# VlakecRemote.net
KiCad netlist of a schematic drawn in Altium Designer
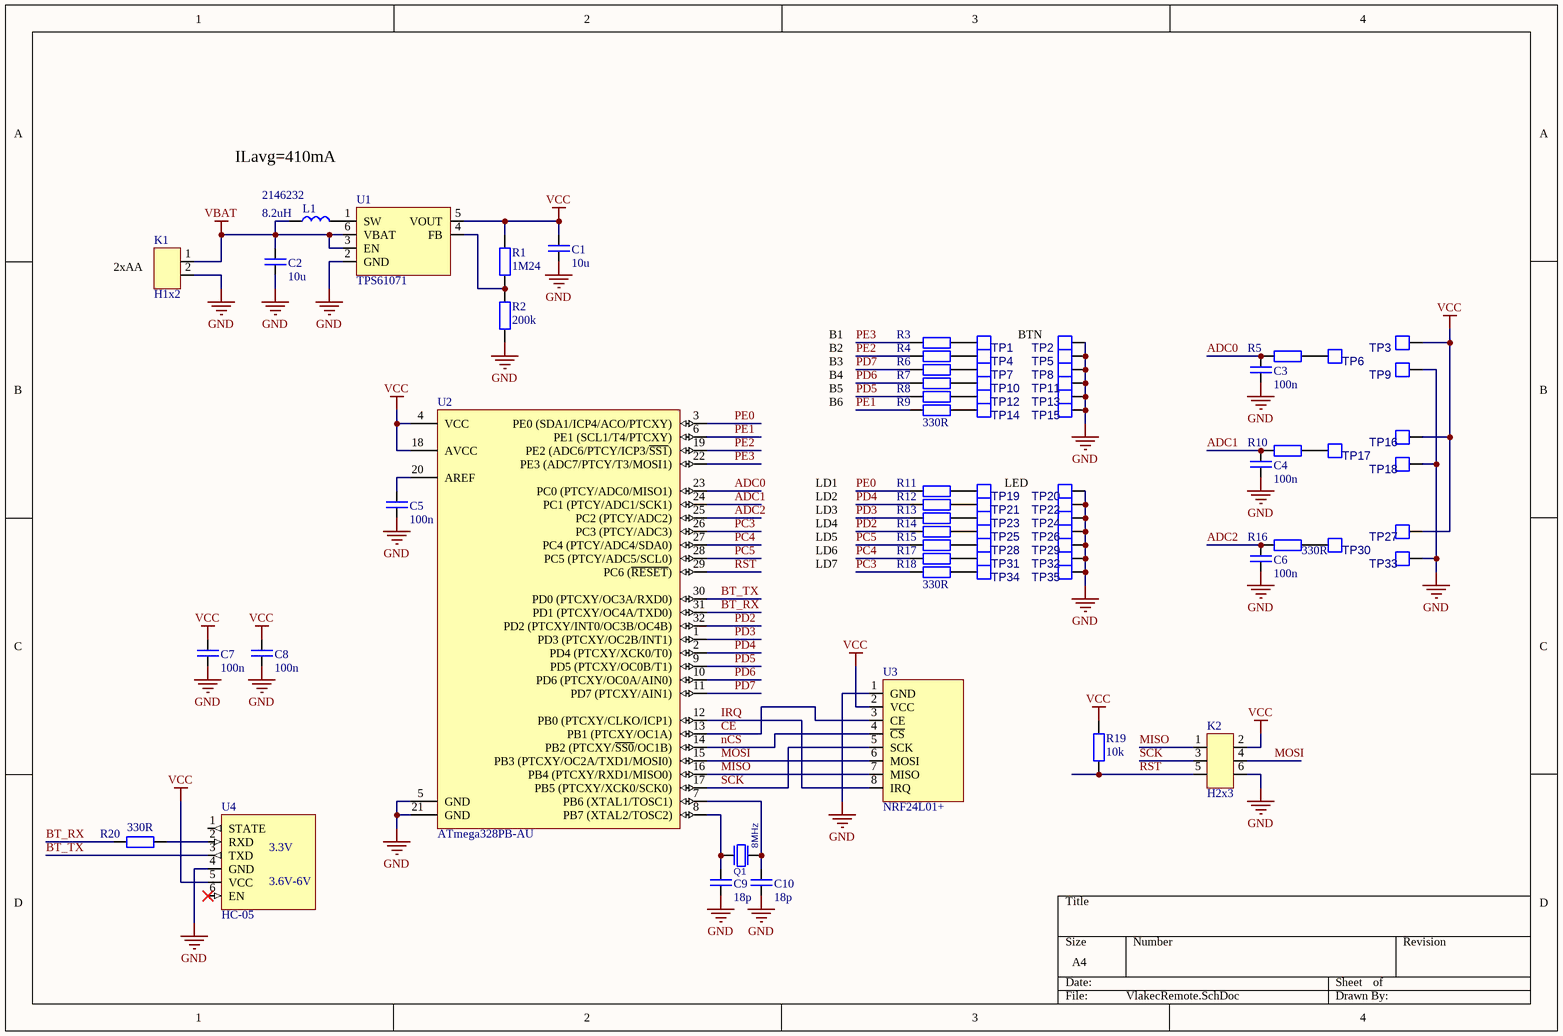
[diagram p0: VlakecRemote.SchDoc]

(export (version "E")
  (design (tool "Eeschema 10.0.6"))
  (components
    (comp (ref "C1")
      (value "10u")
      (footprint "C1206(3216)_N")
      (description "Capacitor")
      (libsource (lib "General") (part "C"))
    )
    (comp (ref "C2")
      (value "10u")
      (footprint "C1206(3216)_N")
      (description "Capacitor")
      (libsource (lib "General") (part "C"))
    )
    (comp (ref "C3")
      (value "100n")
      (footprint "C0805(2012)_N")
      (description "Capacitor")
      (libsource (lib "General") (part "C"))
    )
    (comp (ref "C4")
      (value "100n")
      (footprint "C0805(2012)_N")
      (description "Capacitor")
      (libsource (lib "General") (part "C"))
    )
    (comp (ref "C5")
      (value "100n")
      (footprint "C0805(2012)_N")
      (description "Capacitor")
      (libsource (lib "General") (part "C"))
    )
    (comp (ref "C6")
      (value "100n")
      (footprint "C0805(2012)_N")
      (description "Capacitor")
      (libsource (lib "General") (part "C"))
    )
    (comp (ref "C7")
      (value "100n")
      (footprint "C0805(2012)_N")
      (description "Capacitor")
      (libsource (lib "General") (part "C"))
    )
    (comp (ref "C8")
      (value "100n")
      (footprint "C0805(2012)_N")
      (description "Capacitor")
      (libsource (lib "General") (part "C"))
    )
    (comp (ref "C9")
      (value "18p")
      (footprint "C0805(2012)_N")
      (description "Capacitor")
      (libsource (lib "General") (part "C"))
    )
    (comp (ref "C10")
      (value "18p")
      (footprint "C0805(2012)_N")
      (description "Capacitor")
      (libsource (lib "General") (part "C"))
    )
    (comp (ref "K1")
      (value "H1x2")
      (footprint "H1x2")
      (description "Header 1x2 (male)")
      (libsource (lib "Kon_Tipk") (part "H1x2"))
    )
    (comp (ref "K2")
      (value "H2x3")
      (footprint "H2X3_SPEEDY")
      (description "Header 2x3 (male)")
      (libsource (lib "Kon_Tipk") (part "H2x3"))
    )
    (comp (ref "L1")
      (value "8.2uH")
      (footprint "L2424_6060_M")
      (description "L")
      (fields (field (name "SUPPLIER PART NUMBER 1") "2146232"))
      (libsource (lib "General") (part "L"))
    )
    (comp (ref "Q1")
      (value "8MHz")
      (footprint "Crystal_HC49")
      (description "Crystal")
      (libsource (lib "General") (part "Crystal"))
    )
    (comp (ref "R1")
      (value "1M24")
      (footprint "R0805(2012)_M")
      (description "R")
      (libsource (lib "General") (part "R"))
    )
    (comp (ref "R2")
      (value "200k")
      (footprint "R0805(2012)_M")
      (description "R")
      (libsource (lib "General") (part "R"))
    )
    (comp (ref "R3")
      (value "330R")
      (footprint "R0805(2012)_N")
      (description "R")
      (libsource (lib "General") (part "R"))
    )
    (comp (ref "R4")
      (value "330R")
      (footprint "R0805(2012)_N")
      (description "R")
      (libsource (lib "General") (part "R"))
    )
    (comp (ref "R5")
      (value "330R")
      (footprint "R0805(2012)_N")
      (description "R")
      (libsource (lib "General") (part "R"))
    )
    (comp (ref "R6")
      (value "330R")
      (footprint "R0805(2012)_N")
      (description "R")
      (libsource (lib "General") (part "R"))
    )
    (comp (ref "R7")
      (value "330R")
      (footprint "R0805(2012)_N")
      (description "R")
      (libsource (lib "General") (part "R"))
    )
    (comp (ref "R8")
      (value "330R")
      (footprint "R0805(2012)_N")
      (description "R")
      (libsource (lib "General") (part "R"))
    )
    (comp (ref "R9")
      (value "330R")
      (footprint "R0805(2012)_N")
      (description "R")
      (libsource (lib "General") (part "R"))
    )
    (comp (ref "R10")
      (value "330R")
      (footprint "R0805(2012)_N")
      (description "R")
      (libsource (lib "General") (part "R"))
    )
    (comp (ref "R11")
      (value "330R")
      (footprint "R0805(2012)_N")
      (description "R")
      (libsource (lib "General") (part "R"))
    )
    (comp (ref "R12")
      (value "330R")
      (footprint "R0805(2012)_N")
      (description "R")
      (libsource (lib "General") (part "R"))
    )
    (comp (ref "R13")
      (value "330R")
      (footprint "R0805(2012)_N")
      (description "R")
      (libsource (lib "General") (part "R"))
    )
    (comp (ref "R14")
      (value "330R")
      (footprint "R0805(2012)_N")
      (description "R")
      (libsource (lib "General") (part "R"))
    )
    (comp (ref "R15")
      (value "330R")
      (footprint "R0805(2012)_N")
      (description "R")
      (libsource (lib "General") (part "R"))
    )
    (comp (ref "R16")
      (value "330R")
      (footprint "R0805(2012)_N")
      (description "R")
      (libsource (lib "General") (part "R"))
    )
    (comp (ref "R17")
      (value "330R")
      (footprint "R0805(2012)_N")
      (description "R")
      (libsource (lib "General") (part "R"))
    )
    (comp (ref "R18")
      (value "330R")
      (footprint "R0805(2012)_N")
      (description "R")
      (libsource (lib "General") (part "R"))
    )
    (comp (ref "R19")
      (value "10k")
      (footprint "R0805(2012)_N")
      (description "R")
      (libsource (lib "General") (part "R"))
    )
    (comp (ref "R20")
      (value "330R")
      (footprint "R0805(2012)_N")
      (description "R")
      (libsource (lib "General") (part "R"))
    )
    (comp (ref "TP1") (value "PAD") (footprint "PAD_HOLE") (libsource (lib "General") (part "PAD")))
    (comp (ref "TP2") (value "PAD") (footprint "PAD_HOLE") (libsource (lib "General") (part "PAD")))
    (comp (ref "TP3") (value "PAD") (footprint "PAD_HOLE") (libsource (lib "General") (part "PAD")))
    (comp (ref "TP4") (value "PAD") (footprint "PAD_HOLE") (libsource (lib "General") (part "PAD")))
    (comp (ref "TP5") (value "PAD") (footprint "PAD_HOLE") (libsource (lib "General") (part "PAD")))
    (comp (ref "TP6") (value "PAD") (footprint "PAD_HOLE") (libsource (lib "General") (part "PAD")))
    (comp (ref "TP7") (value "PAD") (footprint "PAD_HOLE") (libsource (lib "General") (part "PAD")))
    (comp (ref "TP8") (value "PAD") (footprint "PAD_HOLE") (libsource (lib "General") (part "PAD")))
    (comp (ref "TP9") (value "PAD") (footprint "PAD_HOLE") (libsource (lib "General") (part "PAD")))
    (comp (ref "TP10") (value "PAD") (footprint "PAD_HOLE") (libsource (lib "General") (part "PAD")))
    (comp (ref "TP11") (value "PAD") (footprint "PAD_HOLE") (libsource (lib "General") (part "PAD")))
    (comp (ref "TP12") (value "PAD") (footprint "PAD_HOLE") (libsource (lib "General") (part "PAD")))
    (comp (ref "TP13") (value "PAD") (footprint "PAD_HOLE") (libsource (lib "General") (part "PAD")))
    (comp (ref "TP14") (value "PAD") (footprint "PAD_HOLE") (libsource (lib "General") (part "PAD")))
    (comp (ref "TP15") (value "PAD") (footprint "PAD_HOLE") (libsource (lib "General") (part "PAD")))
    (comp (ref "TP16") (value "PAD") (footprint "PAD_HOLE") (libsource (lib "General") (part "PAD")))
    (comp (ref "TP17") (value "PAD") (footprint "PAD_HOLE") (libsource (lib "General") (part "PAD")))
    (comp (ref "TP18") (value "PAD") (footprint "PAD_HOLE") (libsource (lib "General") (part "PAD")))
    (comp (ref "TP19") (value "PAD") (footprint "PAD_HOLE") (libsource (lib "General") (part "PAD")))
    (comp (ref "TP20") (value "PAD") (footprint "PAD_HOLE") (libsource (lib "General") (part "PAD")))
    (comp (ref "TP21") (value "PAD") (footprint "PAD_HOLE") (libsource (lib "General") (part "PAD")))
    (comp (ref "TP22") (value "PAD") (footprint "PAD_HOLE") (libsource (lib "General") (part "PAD")))
    (comp (ref "TP23") (value "PAD") (footprint "PAD_HOLE") (libsource (lib "General") (part "PAD")))
    (comp (ref "TP24") (value "PAD") (footprint "PAD_HOLE") (libsource (lib "General") (part "PAD")))
    (comp (ref "TP25") (value "PAD") (footprint "PAD_HOLE") (libsource (lib "General") (part "PAD")))
    (comp (ref "TP26") (value "PAD") (footprint "PAD_HOLE") (libsource (lib "General") (part "PAD")))
    (comp (ref "TP27") (value "PAD") (footprint "PAD_HOLE") (libsource (lib "General") (part "PAD")))
    (comp (ref "TP28") (value "PAD") (footprint "PAD_HOLE") (libsource (lib "General") (part "PAD")))
    (comp (ref "TP29") (value "PAD") (footprint "PAD_HOLE") (libsource (lib "General") (part "PAD")))
    (comp (ref "TP30") (value "PAD") (footprint "PAD_HOLE") (libsource (lib "General") (part "PAD")))
    (comp (ref "TP31") (value "PAD") (footprint "PAD_HOLE") (libsource (lib "General") (part "PAD")))
    (comp (ref "TP32") (value "PAD") (footprint "PAD_HOLE") (libsource (lib "General") (part "PAD")))
    (comp (ref "TP33") (value "PAD") (footprint "PAD_HOLE") (libsource (lib "General") (part "PAD")))
    (comp (ref "TP34") (value "PAD") (footprint "PAD_HOLE") (libsource (lib "General") (part "PAD")))
    (comp (ref "TP35") (value "PAD") (footprint "PAD_HOLE") (libsource (lib "General") (part "PAD")))
    (comp (ref "U1")
      (value "TPS61071")
      (footprint "SOT23-6_N")
      (description "Sync. Boost converter")
      (libsource (lib "ICgeneral") (part "TPS61071"))
    )
    (comp (ref "U2")
      (value "ATmega328PB-AU")
      (footprint "32A_N")
      (libsource (lib "MiskoLIB") (part "ATmega328PB-AU"))
    )
    (comp (ref "U3")
      (value "NRF24L01+")
      (footprint "NRF24L01+tht_module")
      (libsource (lib "Vlakec") (part "NRF24L01+"))
    )
    (comp (ref "U4")
      (value "HC-05")
      (footprint "HC05-horizontal-direct")
      (libsource (lib "Modules") (part "HC-05"))
    )
  )
  (nets
    (net (code "1") (name "/ADC0") (class "Default")
      (node (ref "C3") (pin "1") (pinfunction "1_1") (pintype "passive"))
      (node (ref "R5") (pin "1") (pintype "passive"))
      (node (ref "U2") (pin "23") (pinfunction "PC0_(PTCY/ADC0/MISO1)_23") (pintype "bidirectional"))
    )
    (net (code "2") (name "/ADC1") (class "Default")
      (node (ref "C4") (pin "1") (pinfunction "1_1") (pintype "passive"))
      (node (ref "R10") (pin "1") (pintype "passive"))
      (node (ref "U2") (pin "24") (pinfunction "PC1_(PTCY/ADC1/SCK1)_24") (pintype "bidirectional"))
    )
    (net (code "3") (name "/ADC2") (class "Default")
      (node (ref "C6") (pin "1") (pinfunction "1_1") (pintype "passive"))
      (node (ref "R16") (pin "1") (pintype "passive"))
      (node (ref "U2") (pin "25") (pinfunction "PC2_(PTCY/ADC2)_25") (pintype "bidirectional"))
    )
    (net (code "4") (name "/BT_RX") (class "Default")
      (node (ref "R20") (pin "1") (pintype "passive"))
      (node (ref "U2") (pin "31") (pinfunction "PD1_(PTCXY/OC4A/TXD0)_31") (pintype "bidirectional"))
    )
    (net (code "5") (name "/BT_TX") (class "Default")
      (node (ref "U2") (pin "30") (pinfunction "PD0_(PTCXY/OC3A/RXD0)_30") (pintype "bidirectional"))
      (node (ref "U4") (pin "3") (pinfunction "TXD_3") (pintype "output"))
    )
    (net (code "6") (name "/CE") (class "Default")
      (node (ref "U2") (pin "13") (pinfunction "PB1_(PTCXY/OC1A)_13") (pintype "bidirectional"))
      (node (ref "U3") (pin "3") (pinfunction "CE_3") (pintype "passive"))
    )
    (net (code "7") (name "/IRQ") (class "Default")
      (node (ref "U2") (pin "12") (pinfunction "PB0_(PTCXY/CLKO/ICP1)_12") (pintype "bidirectional"))
      (node (ref "U3") (pin "8") (pinfunction "IRQ_8") (pintype "passive"))
    )
    (net (code "8") (name "/MISO") (class "Default")
      (node (ref "K2") (pin "1") (pinfunction "1_1") (pintype "passive"))
      (node (ref "U2") (pin "16") (pinfunction "PB4_(PTCXY/RXD1/MISO0)_16") (pintype "bidirectional"))
      (node (ref "U3") (pin "7") (pinfunction "MISO_7") (pintype "passive"))
    )
    (net (code "9") (name "/MOSI") (class "Default")
      (node (ref "K2") (pin "4") (pinfunction "4_4") (pintype "passive"))
      (node (ref "U2") (pin "15") (pinfunction "PB3_(PTCXY/OC2A/TXD1/MOSI0)_15") (pintype "bidirectional"))
      (node (ref "U3") (pin "6") (pinfunction "MOSI_6") (pintype "passive"))
    )
    (net (code "10") (name "/PC3") (class "Default")
      (node (ref "R18") (pin "1") (pintype "passive"))
      (node (ref "U2") (pin "26") (pinfunction "PC3_(PTCY/ADC3)_26") (pintype "bidirectional"))
    )
    (net (code "11") (name "/PC4") (class "Default")
      (node (ref "R17") (pin "1") (pintype "passive"))
      (node (ref "U2") (pin "27") (pinfunction "PC4_(PTCY/ADC4/SDA0)_27") (pintype "bidirectional"))
    )
    (net (code "12") (name "/PC5") (class "Default")
      (node (ref "R15") (pin "1") (pintype "passive"))
      (node (ref "U2") (pin "28") (pinfunction "PC5_(PTCY/ADC5/SCL0)_28") (pintype "bidirectional"))
    )
    (net (code "13") (name "/PD2") (class "Default")
      (node (ref "R14") (pin "1") (pintype "passive"))
      (node (ref "U2") (pin "32") (pinfunction "PD2_(PTCXY/INT0/OC3B/OC4B)_32") (pintype "bidirectional"))
    )
    (net (code "14") (name "/PD3") (class "Default")
      (node (ref "R13") (pin "1") (pintype "passive"))
      (node (ref "U2") (pin "1") (pinfunction "PD3_(PTCXY/OC2B/INT1)_1") (pintype "bidirectional"))
    )
    (net (code "15") (name "/PD4") (class "Default")
      (node (ref "R12") (pin "1") (pintype "passive"))
      (node (ref "U2") (pin "2") (pinfunction "PD4_(PTCXY/XCK0/T0)_2") (pintype "bidirectional"))
    )
    (net (code "16") (name "/PD5") (class "Default")
      (node (ref "R8") (pin "1") (pintype "passive"))
      (node (ref "U2") (pin "9") (pinfunction "PD5_(PTCXY/OC0B/T1)_9") (pintype "bidirectional"))
    )
    (net (code "17") (name "/PD6") (class "Default")
      (node (ref "R7") (pin "1") (pintype "passive"))
      (node (ref "U2") (pin "10") (pinfunction "PD6_(PTCXY/OC0A/AIN0)_10") (pintype "bidirectional"))
    )
    (net (code "18") (name "/PD7") (class "Default")
      (node (ref "R6") (pin "1") (pintype "passive"))
      (node (ref "U2") (pin "11") (pinfunction "PD7_(PTCXY/AIN1)_11") (pintype "bidirectional"))
    )
    (net (code "19") (name "/PE0") (class "Default")
      (node (ref "R11") (pin "1") (pintype "passive"))
      (node (ref "U2") (pin "3") (pinfunction "PE0_(SDA1/ICP4/ACO/PTCXY)_3") (pintype "bidirectional"))
    )
    (net (code "20") (name "/PE1") (class "Default")
      (node (ref "R9") (pin "1") (pintype "passive"))
      (node (ref "U2") (pin "6") (pinfunction "PE1_(SCL1/T4/PTCXY)_6") (pintype "bidirectional"))
    )
    (net (code "21") (name "/PE2") (class "Default")
      (node (ref "R4") (pin "1") (pintype "passive"))
      (node (ref "U2") (pin "19") (pinfunction "PE2_(ADC6/PTCY/ICP3/~{SS1})_19") (pintype "bidirectional"))
    )
    (net (code "22") (name "/PE3") (class "Default")
      (node (ref "R3") (pin "1") (pintype "passive"))
      (node (ref "U2") (pin "22") (pinfunction "PE3_(ADC7/PTCY/T3/MOSI1)_22") (pintype "bidirectional"))
    )
    (net (code "23") (name "/RST") (class "Default")
      (node (ref "K2") (pin "5") (pinfunction "5_5") (pintype "passive"))
      (node (ref "R19") (pin "1") (pintype "passive"))
      (node (ref "U2") (pin "29") (pinfunction "PC6_(~{RESET})_29") (pintype "bidirectional"))
    )
    (net (code "24") (name "/SCK") (class "Default")
      (node (ref "K2") (pin "3") (pinfunction "3_3") (pintype "passive"))
      (node (ref "U2") (pin "17") (pinfunction "PB5_(PTCXY/XCK0/SCK0)_17") (pintype "bidirectional"))
      (node (ref "U3") (pin "5") (pinfunction "SCK_5") (pintype "passive"))
    )
    (net (code "25") (name "/nCS") (class "Default")
      (node (ref "U2") (pin "14") (pinfunction "PB2_(PTCXY/~{SS0}/OC1B)_14") (pintype "bidirectional"))
      (node (ref "U3") (pin "4") (pinfunction "~{CS}_4") (pintype "passive"))
    )
    (net (code "26") (name "GND") (class "Default")
      (node (ref "C1") (pin "2") (pinfunction "2_2") (pintype "passive"))
      (node (ref "C10") (pin "2") (pinfunction "2_2") (pintype "passive"))
      (node (ref "C2") (pin "2") (pinfunction "2_2") (pintype "passive"))
      (node (ref "C3") (pin "2") (pinfunction "2_2") (pintype "passive"))
      (node (ref "C4") (pin "2") (pinfunction "2_2") (pintype "passive"))
      (node (ref "C5") (pin "2") (pinfunction "2_2") (pintype "passive"))
      (node (ref "C6") (pin "2") (pinfunction "2_2") (pintype "passive"))
      (node (ref "C7") (pin "2") (pinfunction "2_2") (pintype "passive"))
      (node (ref "C8") (pin "2") (pinfunction "2_2") (pintype "passive"))
      (node (ref "C9") (pin "2") (pinfunction "2_2") (pintype "passive"))
      (node (ref "K1") (pin "2") (pinfunction "2_2") (pintype "passive"))
      (node (ref "K2") (pin "6") (pinfunction "6_6") (pintype "passive"))
      (node (ref "R2") (pin "2") (pintype "passive"))
      (node (ref "TP11") (pin "1") (pinfunction "1_1") (pintype "passive"))
      (node (ref "TP13") (pin "1") (pinfunction "1_1") (pintype "passive"))
      (node (ref "TP15") (pin "1") (pinfunction "1_1") (pintype "passive"))
      (node (ref "TP18") (pin "1") (pinfunction "1_1") (pintype "passive"))
      (node (ref "TP2") (pin "1") (pinfunction "1_1") (pintype "passive"))
      (node (ref "TP20") (pin "1") (pinfunction "1_1") (pintype "passive"))
      (node (ref "TP22") (pin "1") (pinfunction "1_1") (pintype "passive"))
      (node (ref "TP24") (pin "1") (pinfunction "1_1") (pintype "passive"))
      (node (ref "TP26") (pin "1") (pinfunction "1_1") (pintype "passive"))
      (node (ref "TP29") (pin "1") (pinfunction "1_1") (pintype "passive"))
      (node (ref "TP32") (pin "1") (pinfunction "1_1") (pintype "passive"))
      (node (ref "TP33") (pin "1") (pinfunction "1_1") (pintype "passive"))
      (node (ref "TP35") (pin "1") (pinfunction "1_1") (pintype "passive"))
      (node (ref "TP5") (pin "1") (pinfunction "1_1") (pintype "passive"))
      (node (ref "TP8") (pin "1") (pinfunction "1_1") (pintype "passive"))
      (node (ref "TP9") (pin "1") (pinfunction "1_1") (pintype "passive"))
      (node (ref "U1") (pin "2") (pinfunction "GND_2") (pintype "passive"))
      (node (ref "U2") (pin "21") (pinfunction "GND_21") (pintype "power_in"))
      (node (ref "U2") (pin "5") (pinfunction "GND_5") (pintype "power_in"))
      (node (ref "U3") (pin "1") (pinfunction "GND_1") (pintype "passive"))
      (node (ref "U4") (pin "4") (pinfunction "GND_4") (pintype "power_in"))
    )
    (net (code "27") (name "Net-(R3-Pad2)") (class "Default")
      (node (ref "R3") (pin "2") (pintype "passive"))
      (node (ref "TP1") (pin "1") (pinfunction "1_1") (pintype "passive"))
    )
    (net (code "28") (name "Net-(R4-Pad2)") (class "Default")
      (node (ref "R4") (pin "2") (pintype "passive"))
      (node (ref "TP4") (pin "1") (pinfunction "1_1") (pintype "passive"))
    )
    (net (code "29") (name "Net-(R5-Pad2)") (class "Default")
      (node (ref "R5") (pin "2") (pintype "passive"))
      (node (ref "TP6") (pin "1") (pinfunction "1_1") (pintype "passive"))
    )
    (net (code "30") (name "Net-(R6-Pad2)") (class "Default")
      (node (ref "R6") (pin "2") (pintype "passive"))
      (node (ref "TP7") (pin "1") (pinfunction "1_1") (pintype "passive"))
    )
    (net (code "31") (name "Net-(R7-Pad2)") (class "Default")
      (node (ref "R7") (pin "2") (pintype "passive"))
      (node (ref "TP10") (pin "1") (pinfunction "1_1") (pintype "passive"))
    )
    (net (code "32") (name "Net-(R8-Pad2)") (class "Default")
      (node (ref "R8") (pin "2") (pintype "passive"))
      (node (ref "TP12") (pin "1") (pinfunction "1_1") (pintype "passive"))
    )
    (net (code "33") (name "Net-(R9-Pad2)") (class "Default")
      (node (ref "R9") (pin "2") (pintype "passive"))
      (node (ref "TP14") (pin "1") (pinfunction "1_1") (pintype "passive"))
    )
    (net (code "34") (name "Net-(R10-Pad2)") (class "Default")
      (node (ref "R10") (pin "2") (pintype "passive"))
      (node (ref "TP17") (pin "1") (pinfunction "1_1") (pintype "passive"))
    )
    (net (code "35") (name "Net-(R11-Pad2)") (class "Default")
      (node (ref "R11") (pin "2") (pintype "passive"))
      (node (ref "TP19") (pin "1") (pinfunction "1_1") (pintype "passive"))
    )
    (net (code "36") (name "Net-(R12-Pad2)") (class "Default")
      (node (ref "R12") (pin "2") (pintype "passive"))
      (node (ref "TP21") (pin "1") (pinfunction "1_1") (pintype "passive"))
    )
    (net (code "37") (name "Net-(R13-Pad2)") (class "Default")
      (node (ref "R13") (pin "2") (pintype "passive"))
      (node (ref "TP23") (pin "1") (pinfunction "1_1") (pintype "passive"))
    )
    (net (code "38") (name "Net-(R14-Pad2)") (class "Default")
      (node (ref "R14") (pin "2") (pintype "passive"))
      (node (ref "TP25") (pin "1") (pinfunction "1_1") (pintype "passive"))
    )
    (net (code "39") (name "Net-(R15-Pad2)") (class "Default")
      (node (ref "R15") (pin "2") (pintype "passive"))
      (node (ref "TP28") (pin "1") (pinfunction "1_1") (pintype "passive"))
    )
    (net (code "40") (name "Net-(R16-Pad2)") (class "Default")
      (node (ref "R16") (pin "2") (pintype "passive"))
      (node (ref "TP30") (pin "1") (pinfunction "1_1") (pintype "passive"))
    )
    (net (code "41") (name "Net-(R17-Pad2)") (class "Default")
      (node (ref "R17") (pin "2") (pintype "passive"))
      (node (ref "TP31") (pin "1") (pinfunction "1_1") (pintype "passive"))
    )
    (net (code "42") (name "Net-(R18-Pad2)") (class "Default")
      (node (ref "R18") (pin "2") (pintype "passive"))
      (node (ref "TP34") (pin "1") (pinfunction "1_1") (pintype "passive"))
    )
    (net (code "43") (name "Net-(U1-FB)") (class "Default")
      (node (ref "R1") (pin "2") (pintype "passive"))
      (node (ref "R2") (pin "1") (pintype "passive"))
      (node (ref "U1") (pin "4") (pinfunction "FB_4") (pintype "passive"))
    )
    (net (code "44") (name "Net-(U1-SW)") (class "Default")
      (node (ref "L1") (pin "2") (pintype "passive"))
      (node (ref "U1") (pin "1") (pinfunction "SW_1") (pintype "passive"))
    )
    (net (code "45") (name "Net-(U2-AREF)") (class "Default")
      (node (ref "C5") (pin "1") (pinfunction "1_1") (pintype "passive"))
      (node (ref "U2") (pin "20") (pinfunction "AREF_20") (pintype "passive"))
    )
    (net (code "46") (name "Net-(U2-PB6_(XTAL1{slash}TOSC1))") (class "Default")
      (node (ref "C10") (pin "1") (pinfunction "1_1") (pintype "passive"))
      (node (ref "Q1") (pin "2") (pinfunction "2_2") (pintype "passive"))
      (node (ref "U2") (pin "7") (pinfunction "PB6_(XTAL1/TOSC1)_7") (pintype "bidirectional"))
    )
    (net (code "47") (name "Net-(U2-PB7_(XTAL2{slash}TOSC2))") (class "Default")
      (node (ref "C9") (pin "1") (pinfunction "1_1") (pintype "passive"))
      (node (ref "Q1") (pin "1") (pinfunction "1_1") (pintype "passive"))
      (node (ref "U2") (pin "8") (pinfunction "PB7_(XTAL2/TOSC2)_8") (pintype "bidirectional"))
    )
    (net (code "48") (name "Net-(U4-RXD)") (class "Default")
      (node (ref "R20") (pin "2") (pintype "passive"))
      (node (ref "U4") (pin "2") (pinfunction "RXD_2") (pintype "input"))
    )
    (net (code "49") (name "VBAT") (class "Default")
      (node (ref "C2") (pin "1") (pinfunction "1_1") (pintype "passive"))
      (node (ref "K1") (pin "1") (pinfunction "1_1") (pintype "passive"))
      (node (ref "L1") (pin "1") (pintype "passive"))
      (node (ref "U1") (pin "3") (pinfunction "EN_3") (pintype "passive"))
      (node (ref "U1") (pin "6") (pinfunction "VBAT_6") (pintype "passive"))
    )
    (net (code "50") (name "VCC") (class "Default")
      (node (ref "C1") (pin "1") (pinfunction "1_1") (pintype "passive"))
      (node (ref "C7") (pin "1") (pinfunction "1_1") (pintype "passive"))
      (node (ref "C8") (pin "1") (pinfunction "1_1") (pintype "passive"))
      (node (ref "K2") (pin "2") (pinfunction "2_2") (pintype "passive"))
      (node (ref "R1") (pin "1") (pintype "passive"))
      (node (ref "R19") (pin "2") (pintype "passive"))
      (node (ref "TP16") (pin "1") (pinfunction "1_1") (pintype "passive"))
      (node (ref "TP27") (pin "1") (pinfunction "1_1") (pintype "passive"))
      (node (ref "TP3") (pin "1") (pinfunction "1_1") (pintype "passive"))
      (node (ref "U1") (pin "5") (pinfunction "VOUT_5") (pintype "passive"))
      (node (ref "U2") (pin "18") (pinfunction "AVCC_18") (pintype "power_in"))
      (node (ref "U2") (pin "4") (pinfunction "VCC_4") (pintype "power_in"))
      (node (ref "U3") (pin "2") (pinfunction "VCC_2") (pintype "passive"))
      (node (ref "U4") (pin "5") (pinfunction "VCC_5") (pintype "power_in"))
    )
    (net (code "51") (name "unconnected-(U4-EN-Pad6)") (class "Default")
      (node (ref "U4") (pin "6") (pinfunction "EN_6") (pintype "input+no_connect"))
    )
    (net (code "52") (name "unconnected-(U4-STATE-Pad1)") (class "Default")
      (node (ref "U4") (pin "1") (pinfunction "STATE_1") (pintype "output"))
    )
  )
)
